# Power_Pins_Page_RV1126.net
KiCad netlist of a schematic drawn in Altium Designer
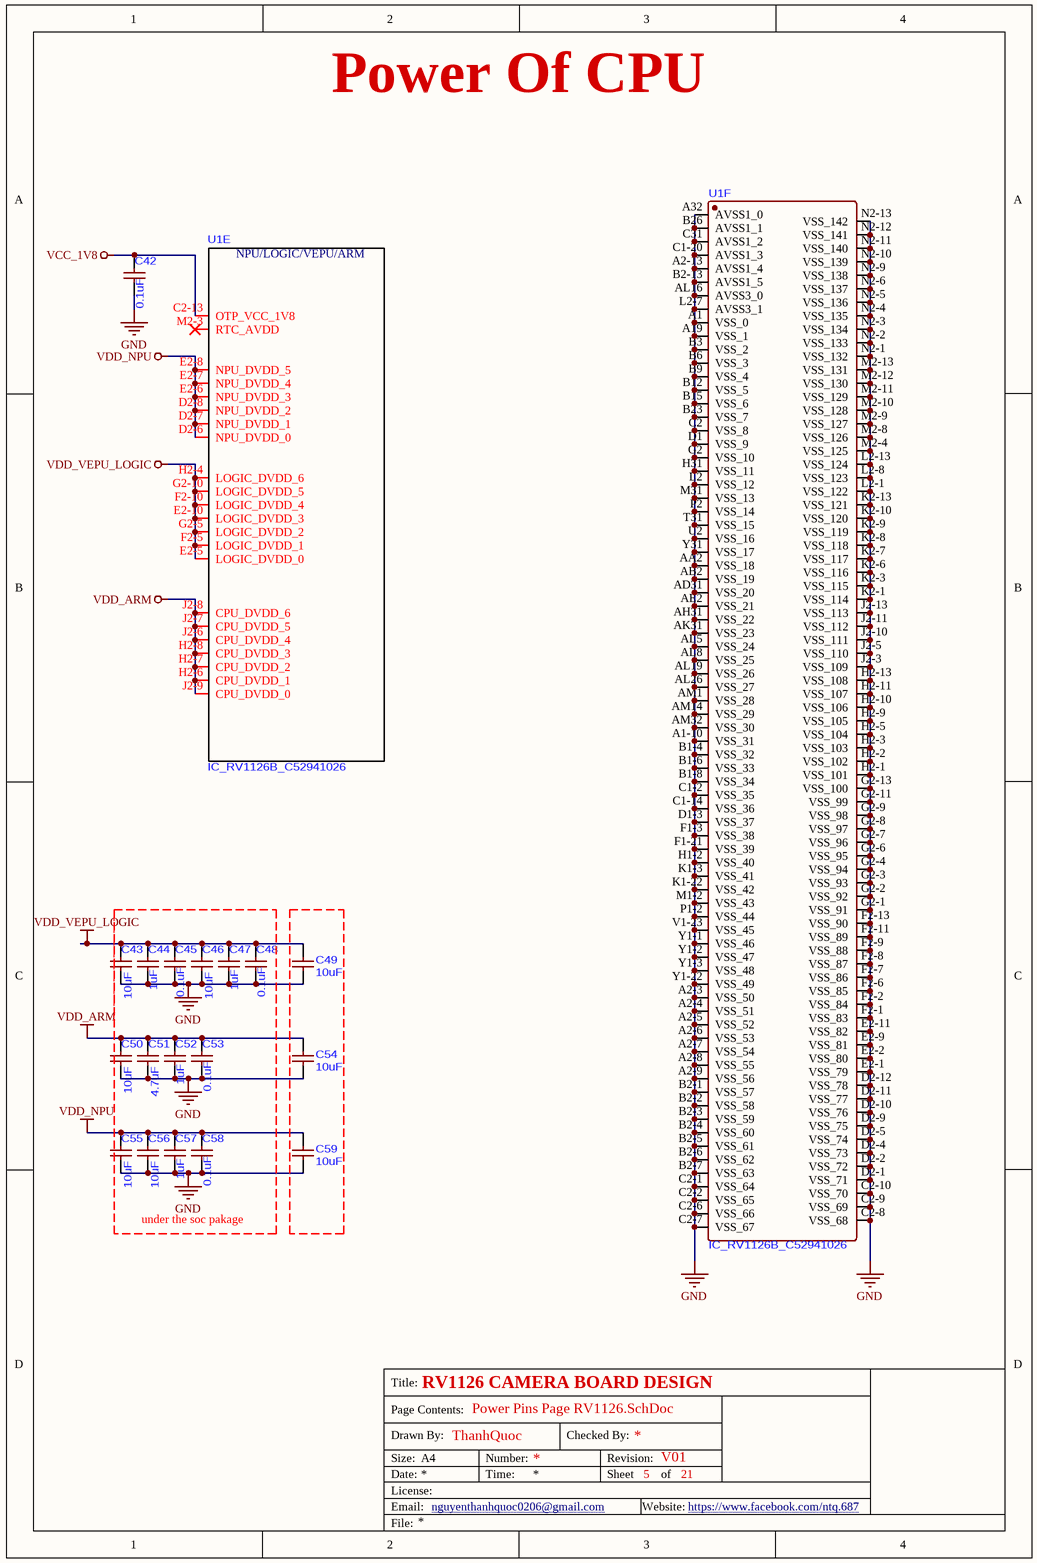
[diagram p0: Power Pins Page RV1126.SchDoc]

(export (version "E")
  (design (tool "Eeschema 10.0.6"))
  (components
    (comp (ref "C42")
      (value "0.1uF")
      (footprint "C0201")
      (description "0.1uF ±10% 6.3V Ceramic Capacitor X5R 0201")
      (libsource (lib "Schlib1") (part "CAP_100nF-6.3V-10%-0201_1"))
    )
    (comp (ref "C43")
      (value "10uF")
      (footprint "C0402")
      (description "10µF ±20% 10V Ceramic Capacitor X5R 0402 (1005 Metric)")
      (libsource (lib "Schlib1") (part "CAP_10uF-10V-20%-0402"))
    )
    (comp (ref "C44")
      (value "1uF")
      (footprint "C0201")
      (description "1uF ±10% 6.3V Ceramic Capacitor X5R 0201")
      (libsource (lib "Schlib1") (part "CAP_1uF-6.3V-10%-0201"))
    )
    (comp (ref "C45")
      (value "0.1uF")
      (footprint "C0201")
      (description "0.1uF ±10% 6.3V Ceramic Capacitor X5R 0201")
      (libsource (lib "Schlib1") (part "CAP_100nF-6.3V-10%-0201_1"))
    )
    (comp (ref "C46")
      (value "10uF")
      (footprint "C0402")
      (description "10µF ±20% 10V Ceramic Capacitor X5R 0402 (1005 Metric)")
      (libsource (lib "Schlib1") (part "CAP_10uF-10V-20%-0402"))
    )
    (comp (ref "C47")
      (value "1uF")
      (footprint "C0201")
      (description "1uF ±10% 6.3V Ceramic Capacitor X5R 0201")
      (libsource (lib "Schlib1") (part "CAP_1uF-6.3V-10%-0201"))
    )
    (comp (ref "C48")
      (value "0.1uF")
      (footprint "C0201")
      (description "0.1uF ±10% 6.3V Ceramic Capacitor X5R 0201")
      (libsource (lib "Schlib1") (part "CAP_100nF-6.3V-10%-0201_1"))
    )
    (comp (ref "C49")
      (value "10uF")
      (footprint "C0402")
      (description "10µF ±20% 10V Ceramic Capacitor X5R 0402 (1005 Metric)")
      (libsource (lib "Schlib1") (part "CAP_10uF-10V-20%-0402"))
    )
    (comp (ref "C50")
      (value "10uF")
      (footprint "C0402")
      (description "10µF ±20% 10V Ceramic Capacitor X5R 0402 (1005 Metric)")
      (libsource (lib "Schlib1") (part "CAP_10uF-10V-20%-0402"))
    )
    (comp (ref "C51")
      (value "4.7uF")
      (footprint "C0402")
      (description "4.7µF ±10% 10V Ceramic Capacitor X5R 0402 (1005 Metric)")
      (libsource (lib "Schlib1") (part "CAP_4.7uF-10V-10%-0402"))
    )
    (comp (ref "C52")
      (value "1uF")
      (footprint "C0201")
      (description "1uF ±10% 6.3V Ceramic Capacitor X5R 0201")
      (libsource (lib "Schlib1") (part "CAP_1uF-6.3V-10%-0201"))
    )
    (comp (ref "C53")
      (value "0.1uF")
      (footprint "C0201")
      (description "0.1uF ±10% 6.3V Ceramic Capacitor X5R 0201")
      (libsource (lib "Schlib1") (part "CAP_100nF-6.3V-10%-0201_1"))
    )
    (comp (ref "C54")
      (value "10uF")
      (footprint "C0402")
      (description "10µF ±20% 10V Ceramic Capacitor X5R 0402 (1005 Metric)")
      (libsource (lib "Schlib1") (part "CAP_10uF-10V-20%-0402"))
    )
    (comp (ref "C55")
      (value "10uF")
      (footprint "C0402")
      (description "10µF ±20% 10V Ceramic Capacitor X5R 0402 (1005 Metric)")
      (libsource (lib "Schlib1") (part "CAP_10uF-10V-20%-0402"))
    )
    (comp (ref "C56")
      (value "10uF")
      (footprint "C0402")
      (description "10µF ±20% 10V Ceramic Capacitor X5R 0402 (1005 Metric)")
      (libsource (lib "Schlib1") (part "CAP_10uF-10V-20%-0402"))
    )
    (comp (ref "C57")
      (value "1uF")
      (footprint "C0201")
      (description "1uF ±10% 6.3V Ceramic Capacitor X5R 0201")
      (libsource (lib "Schlib1") (part "CAP_1uF-6.3V-10%-0201"))
    )
    (comp (ref "C58")
      (value "0.1uF")
      (footprint "C0201")
      (description "0.1uF ±10% 6.3V Ceramic Capacitor X5R 0201")
      (libsource (lib "Schlib1") (part "CAP_100nF-6.3V-10%-0201_1"))
    )
    (comp (ref "C59")
      (value "10uF")
      (footprint "C0402")
      (description "10µF ±20% 10V Ceramic Capacitor X5R 0402 (1005 Metric)")
      (libsource (lib "Schlib1") (part "CAP_10uF-10V-20%-0402"))
    )
    (comp (ref "U1")
      (value "IC_RV1126B_C52941026")
      (footprint "CCSP-491_L14.0-W14.0-TL_RV1126B")
      (libsource (lib "Schlib1") (part "IC_RV1126B_C52941026"))
    )
  )
  (nets
    (net (code "1") (name "GND") (class "Default")
      (node (ref "C42") (pin "1") (pinfunction "1_1") (pintype "passive"))
      (node (ref "C43") (pin "1") (pinfunction "1_1") (pintype "passive"))
      (node (ref "C44") (pin "1") (pinfunction "1_1") (pintype "passive"))
      (node (ref "C45") (pin "1") (pinfunction "1_1") (pintype "passive"))
      (node (ref "C46") (pin "1") (pinfunction "1_1") (pintype "passive"))
      (node (ref "C47") (pin "1") (pinfunction "1_1") (pintype "passive"))
      (node (ref "C48") (pin "1") (pinfunction "1_1") (pintype "passive"))
      (node (ref "C49") (pin "1") (pinfunction "1_1") (pintype "passive"))
      (node (ref "C50") (pin "1") (pinfunction "1_1") (pintype "passive"))
      (node (ref "C51") (pin "1") (pinfunction "1_1") (pintype "passive"))
      (node (ref "C52") (pin "1") (pinfunction "1_1") (pintype "passive"))
      (node (ref "C53") (pin "1") (pinfunction "1_1") (pintype "passive"))
      (node (ref "C54") (pin "1") (pinfunction "1_1") (pintype "passive"))
      (node (ref "C55") (pin "1") (pinfunction "1_1") (pintype "passive"))
      (node (ref "C56") (pin "1") (pinfunction "1_1") (pintype "passive"))
      (node (ref "C57") (pin "1") (pinfunction "1_1") (pintype "passive"))
      (node (ref "C58") (pin "1") (pinfunction "1_1") (pintype "passive"))
      (node (ref "C59") (pin "1") (pinfunction "1_1") (pintype "passive"))
      (node (ref "U1") (pin "A1") (pinfunction "VSS_0_A1") (pintype "passive"))
      (node (ref "U1") (pin "A1-10") (pinfunction "VSS_31_A1-10") (pintype "passive"))
      (node (ref "U1") (pin "A19") (pinfunction "VSS_1_A19") (pintype "passive"))
      (node (ref "U1") (pin "A2-13") (pinfunction "AVSS1_4_A2-13") (pintype "passive"))
      (node (ref "U1") (pin "A2-3") (pinfunction "VSS_50_A2-3") (pintype "passive"))
      (node (ref "U1") (pin "A2-4") (pinfunction "VSS_51_A2-4") (pintype "passive"))
      (node (ref "U1") (pin "A2-5") (pinfunction "VSS_52_A2-5") (pintype "passive"))
      (node (ref "U1") (pin "A2-6") (pinfunction "VSS_53_A2-6") (pintype "passive"))
      (node (ref "U1") (pin "A2-7") (pinfunction "VSS_54_A2-7") (pintype "passive"))
      (node (ref "U1") (pin "A2-8") (pinfunction "VSS_55_A2-8") (pintype "passive"))
      (node (ref "U1") (pin "A2-9") (pinfunction "VSS_56_A2-9") (pintype "passive"))
      (node (ref "U1") (pin "A32") (pinfunction "AVSS1_0_A32") (pintype "passive"))
      (node (ref "U1") (pin "AA2") (pinfunction "VSS_18_AA2") (pintype "passive"))
      (node (ref "U1") (pin "AB2") (pinfunction "VSS_19_AB2") (pintype "passive"))
      (node (ref "U1") (pin "AD31") (pinfunction "VSS_20_AD31") (pintype "passive"))
      (node (ref "U1") (pin "AE2") (pinfunction "VSS_21_AE2") (pintype "passive"))
      (node (ref "U1") (pin "AH31") (pinfunction "VSS_22_AH31") (pintype "passive"))
      (node (ref "U1") (pin "AK31") (pinfunction "VSS_23_AK31") (pintype "passive"))
      (node (ref "U1") (pin "AL16") (pinfunction "AVSS3_0_AL16") (pintype "passive"))
      (node (ref "U1") (pin "AL19") (pinfunction "VSS_26_AL19") (pintype "passive"))
      (node (ref "U1") (pin "AL26") (pinfunction "VSS_27_AL26") (pintype "passive"))
      (node (ref "U1") (pin "AL5") (pinfunction "VSS_24_AL5") (pintype "passive"))
      (node (ref "U1") (pin "AL8") (pinfunction "VSS_25_AL8") (pintype "passive"))
      (node (ref "U1") (pin "AM1") (pinfunction "VSS_28_AM1") (pintype "passive"))
      (node (ref "U1") (pin "AM14") (pinfunction "VSS_29_AM14") (pintype "passive"))
      (node (ref "U1") (pin "AM32") (pinfunction "VSS_30_AM32") (pintype "passive"))
      (node (ref "U1") (pin "B1-4") (pinfunction "VSS_32_B1-4") (pintype "passive"))
      (node (ref "U1") (pin "B1-6") (pinfunction "VSS_33_B1-6") (pintype "passive"))
      (node (ref "U1") (pin "B1-8") (pinfunction "VSS_34_B1-8") (pintype "passive"))
      (node (ref "U1") (pin "B12") (pinfunction "VSS_5_B12") (pintype "passive"))
      (node (ref "U1") (pin "B15") (pinfunction "VSS_6_B15") (pintype "passive"))
      (node (ref "U1") (pin "B2-1") (pinfunction "VSS_57_B2-1") (pintype "passive"))
      (node (ref "U1") (pin "B2-13") (pinfunction "AVSS1_5_B2-13") (pintype "passive"))
      (node (ref "U1") (pin "B2-2") (pinfunction "VSS_58_B2-2") (pintype "passive"))
      (node (ref "U1") (pin "B2-3") (pinfunction "VSS_59_B2-3") (pintype "passive"))
      (node (ref "U1") (pin "B2-4") (pinfunction "VSS_60_B2-4") (pintype "passive"))
      (node (ref "U1") (pin "B2-5") (pinfunction "VSS_61_B2-5") (pintype "passive"))
      (node (ref "U1") (pin "B2-6") (pinfunction "VSS_62_B2-6") (pintype "passive"))
      (node (ref "U1") (pin "B2-7") (pinfunction "VSS_63_B2-7") (pintype "passive"))
      (node (ref "U1") (pin "B23") (pinfunction "VSS_7_B23") (pintype "passive"))
      (node (ref "U1") (pin "B26") (pinfunction "AVSS1_1_B26") (pintype "passive"))
      (node (ref "U1") (pin "B3") (pinfunction "VSS_2_B3") (pintype "passive"))
      (node (ref "U1") (pin "B6") (pinfunction "VSS_3_B6") (pintype "passive"))
      (node (ref "U1") (pin "B9") (pinfunction "VSS_4_B9") (pintype "passive"))
      (node (ref "U1") (pin "C1-14") (pinfunction "VSS_36_C1-14") (pintype "passive"))
      (node (ref "U1") (pin "C1-2") (pinfunction "VSS_35_C1-2") (pintype "passive"))
      (node (ref "U1") (pin "C1-20") (pinfunction "AVSS1_3_C1-20") (pintype "passive"))
      (node (ref "U1") (pin "C2") (pinfunction "VSS_8_C2") (pintype "passive"))
      (node (ref "U1") (pin "C2-1") (pinfunction "VSS_64_C2-1") (pintype "passive"))
      (node (ref "U1") (pin "C2-10") (pinfunction "VSS_70_C2-10") (pintype "passive"))
      (node (ref "U1") (pin "C2-2") (pinfunction "VSS_65_C2-2") (pintype "passive"))
      (node (ref "U1") (pin "C2-6") (pinfunction "VSS_66_C2-6") (pintype "passive"))
      (node (ref "U1") (pin "C2-7") (pinfunction "VSS_67_C2-7") (pintype "passive"))
      (node (ref "U1") (pin "C2-8") (pinfunction "VSS_68_C2-8") (pintype "passive"))
      (node (ref "U1") (pin "C2-9") (pinfunction "VSS_69_C2-9") (pintype "passive"))
      (node (ref "U1") (pin "C31") (pinfunction "AVSS1_2_C31") (pintype "passive"))
      (node (ref "U1") (pin "D1") (pinfunction "VSS_9_D1") (pintype "passive"))
      (node (ref "U1") (pin "D1-3") (pinfunction "VSS_37_D1-3") (pintype "passive"))
      (node (ref "U1") (pin "D2-1") (pinfunction "VSS_71_D2-1") (pintype "passive"))
      (node (ref "U1") (pin "D2-10") (pinfunction "VSS_76_D2-10") (pintype "passive"))
      (node (ref "U1") (pin "D2-11") (pinfunction "VSS_77_D2-11") (pintype "passive"))
      (node (ref "U1") (pin "D2-12") (pinfunction "VSS_78_D2-12") (pintype "passive"))
      (node (ref "U1") (pin "D2-2") (pinfunction "VSS_72_D2-2") (pintype "passive"))
      (node (ref "U1") (pin "D2-4") (pinfunction "VSS_73_D2-4") (pintype "passive"))
      (node (ref "U1") (pin "D2-5") (pinfunction "VSS_74_D2-5") (pintype "passive"))
      (node (ref "U1") (pin "D2-9") (pinfunction "VSS_75_D2-9") (pintype "passive"))
      (node (ref "U1") (pin "E2-1") (pinfunction "VSS_79_E2-1") (pintype "passive"))
      (node (ref "U1") (pin "E2-11") (pinfunction "VSS_82_E2-11") (pintype "passive"))
      (node (ref "U1") (pin "E2-2") (pinfunction "VSS_80_E2-2") (pintype "passive"))
      (node (ref "U1") (pin "E2-9") (pinfunction "VSS_81_E2-9") (pintype "passive"))
      (node (ref "U1") (pin "F1-21") (pinfunction "VSS_39_F1-21") (pintype "passive"))
      (node (ref "U1") (pin "F1-3") (pinfunction "VSS_38_F1-3") (pintype "passive"))
      (node (ref "U1") (pin "F2-1") (pinfunction "VSS_83_F2-1") (pintype "passive"))
      (node (ref "U1") (pin "F2-11") (pinfunction "VSS_89_F2-11") (pintype "passive"))
      (node (ref "U1") (pin "F2-13") (pinfunction "VSS_90_F2-13") (pintype "passive"))
      (node (ref "U1") (pin "F2-2") (pinfunction "VSS_84_F2-2") (pintype "passive"))
      (node (ref "U1") (pin "F2-6") (pinfunction "VSS_85_F2-6") (pintype "passive"))
      (node (ref "U1") (pin "F2-7") (pinfunction "VSS_86_F2-7") (pintype "passive"))
      (node (ref "U1") (pin "F2-8") (pinfunction "VSS_87_F2-8") (pintype "passive"))
      (node (ref "U1") (pin "F2-9") (pinfunction "VSS_88_F2-9") (pintype "passive"))
      (node (ref "U1") (pin "G2") (pinfunction "VSS_10_G2") (pintype "passive"))
      (node (ref "U1") (pin "G2-1") (pinfunction "VSS_91_G2-1") (pintype "passive"))
      (node (ref "U1") (pin "G2-11") (pinfunction "VSS_99_G2-11") (pintype "passive"))
      (node (ref "U1") (pin "G2-13") (pinfunction "VSS_100_G2-13") (pintype "passive"))
      (node (ref "U1") (pin "G2-2") (pinfunction "VSS_92_G2-2") (pintype "passive"))
      (node (ref "U1") (pin "G2-3") (pinfunction "VSS_93_G2-3") (pintype "passive"))
      (node (ref "U1") (pin "G2-4") (pinfunction "VSS_94_G2-4") (pintype "passive"))
      (node (ref "U1") (pin "G2-6") (pinfunction "VSS_95_G2-6") (pintype "passive"))
      (node (ref "U1") (pin "G2-7") (pinfunction "VSS_96_G2-7") (pintype "passive"))
      (node (ref "U1") (pin "G2-8") (pinfunction "VSS_97_G2-8") (pintype "passive"))
      (node (ref "U1") (pin "G2-9") (pinfunction "VSS_98_G2-9") (pintype "passive"))
      (node (ref "U1") (pin "H1-2") (pinfunction "VSS_40_H1-2") (pintype "passive"))
      (node (ref "U1") (pin "H2-1") (pinfunction "VSS_101_H2-1") (pintype "passive"))
      (node (ref "U1") (pin "H2-10") (pinfunction "VSS_106_H2-10") (pintype "passive"))
      (node (ref "U1") (pin "H2-11") (pinfunction "VSS_107_H2-11") (pintype "passive"))
      (node (ref "U1") (pin "H2-13") (pinfunction "VSS_108_H2-13") (pintype "passive"))
      (node (ref "U1") (pin "H2-2") (pinfunction "VSS_102_H2-2") (pintype "passive"))
      (node (ref "U1") (pin "H2-3") (pinfunction "VSS_103_H2-3") (pintype "passive"))
      (node (ref "U1") (pin "H2-5") (pinfunction "VSS_104_H2-5") (pintype "passive"))
      (node (ref "U1") (pin "H2-9") (pinfunction "VSS_105_H2-9") (pintype "passive"))
      (node (ref "U1") (pin "H31") (pinfunction "VSS_11_H31") (pintype "passive"))
      (node (ref "U1") (pin "J2-10") (pinfunction "VSS_111_J2-10") (pintype "passive"))
      (node (ref "U1") (pin "J2-11") (pinfunction "VSS_112_J2-11") (pintype "passive"))
      (node (ref "U1") (pin "J2-13") (pinfunction "VSS_113_J2-13") (pintype "passive"))
      (node (ref "U1") (pin "J2-3") (pinfunction "VSS_109_J2-3") (pintype "passive"))
      (node (ref "U1") (pin "J2-5") (pinfunction "VSS_110_J2-5") (pintype "passive"))
      (node (ref "U1") (pin "K1-22") (pinfunction "VSS_42_K1-22") (pintype "passive"))
      (node (ref "U1") (pin "K1-3") (pinfunction "VSS_41_K1-3") (pintype "passive"))
      (node (ref "U1") (pin "K2-1") (pinfunction "VSS_114_K2-1") (pintype "passive"))
      (node (ref "U1") (pin "K2-10") (pinfunction "VSS_120_K2-10") (pintype "passive"))
      (node (ref "U1") (pin "K2-13") (pinfunction "VSS_121_K2-13") (pintype "passive"))
      (node (ref "U1") (pin "K2-3") (pinfunction "VSS_115_K2-3") (pintype "passive"))
      (node (ref "U1") (pin "K2-6") (pinfunction "VSS_116_K2-6") (pintype "passive"))
      (node (ref "U1") (pin "K2-7") (pinfunction "VSS_117_K2-7") (pintype "passive"))
      (node (ref "U1") (pin "K2-8") (pinfunction "VSS_118_K2-8") (pintype "passive"))
      (node (ref "U1") (pin "K2-9") (pinfunction "VSS_119_K2-9") (pintype "passive"))
      (node (ref "U1") (pin "L2") (pinfunction "VSS_12_L2") (pintype "passive"))
      (node (ref "U1") (pin "L2-1") (pinfunction "VSS_122_L2-1") (pintype "passive"))
      (node (ref "U1") (pin "L2-13") (pinfunction "VSS_124_L2-13") (pintype "passive"))
      (node (ref "U1") (pin "L2-7") (pinfunction "AVSS3_1_L2-7") (pintype "passive"))
      (node (ref "U1") (pin "L2-8") (pinfunction "VSS_123_L2-8") (pintype "passive"))
      (node (ref "U1") (pin "M1-2") (pinfunction "VSS_43_M1-2") (pintype "passive"))
      (node (ref "U1") (pin "M2-10") (pinfunction "VSS_128_M2-10") (pintype "passive"))
      (node (ref "U1") (pin "M2-11") (pinfunction "VSS_129_M2-11") (pintype "passive"))
      (node (ref "U1") (pin "M2-12") (pinfunction "VSS_130_M2-12") (pintype "passive"))
      (node (ref "U1") (pin "M2-13") (pinfunction "VSS_131_M2-13") (pintype "passive"))
      (node (ref "U1") (pin "M2-4") (pinfunction "VSS_125_M2-4") (pintype "passive"))
      (node (ref "U1") (pin "M2-8") (pinfunction "VSS_126_M2-8") (pintype "passive"))
      (node (ref "U1") (pin "M2-9") (pinfunction "VSS_127_M2-9") (pintype "passive"))
      (node (ref "U1") (pin "M31") (pinfunction "VSS_13_M31") (pintype "passive"))
      (node (ref "U1") (pin "N2-1") (pinfunction "VSS_132_N2-1") (pintype "passive"))
      (node (ref "U1") (pin "N2-10") (pinfunction "VSS_139_N2-10") (pintype "passive"))
      (node (ref "U1") (pin "N2-11") (pinfunction "VSS_140_N2-11") (pintype "passive"))
      (node (ref "U1") (pin "N2-12") (pinfunction "VSS_141_N2-12") (pintype "passive"))
      (node (ref "U1") (pin "N2-13") (pinfunction "VSS_142_N2-13") (pintype "passive"))
      (node (ref "U1") (pin "N2-2") (pinfunction "VSS_133_N2-2") (pintype "passive"))
      (node (ref "U1") (pin "N2-3") (pinfunction "VSS_134_N2-3") (pintype "passive"))
      (node (ref "U1") (pin "N2-4") (pinfunction "VSS_135_N2-4") (pintype "passive"))
      (node (ref "U1") (pin "N2-5") (pinfunction "VSS_136_N2-5") (pintype "passive"))
      (node (ref "U1") (pin "N2-6") (pinfunction "VSS_137_N2-6") (pintype "passive"))
      (node (ref "U1") (pin "N2-9") (pinfunction "VSS_138_N2-9") (pintype "passive"))
      (node (ref "U1") (pin "P1-2") (pinfunction "VSS_44_P1-2") (pintype "passive"))
      (node (ref "U1") (pin "P2") (pinfunction "VSS_14_P2") (pintype "passive"))
      (node (ref "U1") (pin "T31") (pinfunction "VSS_15_T31") (pintype "passive"))
      (node (ref "U1") (pin "U2") (pinfunction "VSS_16_U2") (pintype "passive"))
      (node (ref "U1") (pin "V1-23") (pinfunction "VSS_45_V1-23") (pintype "passive"))
      (node (ref "U1") (pin "Y1-1") (pinfunction "VSS_46_Y1-1") (pintype "passive"))
      (node (ref "U1") (pin "Y1-2") (pinfunction "VSS_47_Y1-2") (pintype "passive"))
      (node (ref "U1") (pin "Y1-22") (pinfunction "VSS_49_Y1-22") (pintype "passive"))
      (node (ref "U1") (pin "Y1-3") (pinfunction "VSS_48_Y1-3") (pintype "passive"))
      (node (ref "U1") (pin "Y31") (pinfunction "VSS_17_Y31") (pintype "passive"))
    )
    (net (code "2") (name "VCC_1V8") (class "Default")
      (node (ref "C42") (pin "2") (pinfunction "2_2") (pintype "passive"))
      (node (ref "U1") (pin "C2-13") (pinfunction "OTP_VCC_1V8_C2-13") (pintype "passive"))
    )
    (net (code "3") (name "VDD_ARM") (class "Default")
      (node (ref "C50") (pin "2") (pinfunction "2_2") (pintype "passive"))
      (node (ref "C51") (pin "2") (pinfunction "2_2") (pintype "passive"))
      (node (ref "C52") (pin "2") (pinfunction "2_2") (pintype "passive"))
      (node (ref "C53") (pin "2") (pinfunction "2_2") (pintype "passive"))
      (node (ref "C54") (pin "2") (pinfunction "2_2") (pintype "passive"))
      (node (ref "U1") (pin "H2-6") (pinfunction "CPU_DVDD_1_H2-6") (pintype "passive"))
      (node (ref "U1") (pin "H2-7") (pinfunction "CPU_DVDD_2_H2-7") (pintype "passive"))
      (node (ref "U1") (pin "H2-8") (pinfunction "CPU_DVDD_3_H2-8") (pintype "passive"))
      (node (ref "U1") (pin "J2-6") (pinfunction "CPU_DVDD_4_J2-6") (pintype "passive"))
      (node (ref "U1") (pin "J2-7") (pinfunction "CPU_DVDD_5_J2-7") (pintype "passive"))
      (node (ref "U1") (pin "J2-8") (pinfunction "CPU_DVDD_6_J2-8") (pintype "passive"))
      (node (ref "U1") (pin "J2-9") (pinfunction "CPU_DVDD_0_J2-9") (pintype "passive"))
    )
    (net (code "4") (name "VDD_NPU") (class "Default")
      (node (ref "C55") (pin "2") (pinfunction "2_2") (pintype "passive"))
      (node (ref "C56") (pin "2") (pinfunction "2_2") (pintype "passive"))
      (node (ref "C57") (pin "2") (pinfunction "2_2") (pintype "passive"))
      (node (ref "C58") (pin "2") (pinfunction "2_2") (pintype "passive"))
      (node (ref "C59") (pin "2") (pinfunction "2_2") (pintype "passive"))
      (node (ref "U1") (pin "D2-6") (pinfunction "NPU_DVDD_0_D2-6") (pintype "passive"))
      (node (ref "U1") (pin "D2-7") (pinfunction "NPU_DVDD_1_D2-7") (pintype "passive"))
      (node (ref "U1") (pin "D2-8") (pinfunction "NPU_DVDD_2_D2-8") (pintype "passive"))
      (node (ref "U1") (pin "E2-6") (pinfunction "NPU_DVDD_3_E2-6") (pintype "passive"))
      (node (ref "U1") (pin "E2-7") (pinfunction "NPU_DVDD_4_E2-7") (pintype "passive"))
      (node (ref "U1") (pin "E2-8") (pinfunction "NPU_DVDD_5_E2-8") (pintype "passive"))
    )
    (net (code "5") (name "VDD_VEPU_LOGIC") (class "Default")
      (node (ref "C43") (pin "2") (pinfunction "2_2") (pintype "passive"))
      (node (ref "C44") (pin "2") (pinfunction "2_2") (pintype "passive"))
      (node (ref "C45") (pin "2") (pinfunction "2_2") (pintype "passive"))
      (node (ref "C46") (pin "2") (pinfunction "2_2") (pintype "passive"))
      (node (ref "C47") (pin "2") (pinfunction "2_2") (pintype "passive"))
      (node (ref "C48") (pin "2") (pinfunction "2_2") (pintype "passive"))
      (node (ref "C49") (pin "2") (pinfunction "2_2") (pintype "passive"))
      (node (ref "U1") (pin "E2-10") (pinfunction "LOGIC_DVDD_3_E2-10") (pintype "passive"))
      (node (ref "U1") (pin "E2-5") (pinfunction "LOGIC_DVDD_0_E2-5") (pintype "passive"))
      (node (ref "U1") (pin "F2-10") (pinfunction "LOGIC_DVDD_4_F2-10") (pintype "passive"))
      (node (ref "U1") (pin "F2-5") (pinfunction "LOGIC_DVDD_1_F2-5") (pintype "passive"))
      (node (ref "U1") (pin "G2-10") (pinfunction "LOGIC_DVDD_5_G2-10") (pintype "passive"))
      (node (ref "U1") (pin "G2-5") (pinfunction "LOGIC_DVDD_2_G2-5") (pintype "passive"))
      (node (ref "U1") (pin "H2-4") (pinfunction "LOGIC_DVDD_6_H2-4") (pintype "passive"))
    )
    (net (code "6") (name "unconnected-(U1E-RTC_AVDD-PadM2-3)") (class "Default")
      (node (ref "U1") (pin "M2-3") (pinfunction "RTC_AVDD_M2-3") (pintype "passive+no_connect"))
    )
  )
)
